# SP26_FindingTitan_Polarization_Circuit_M.net
KiCad netlist of a schematic drawn in Altium Designer
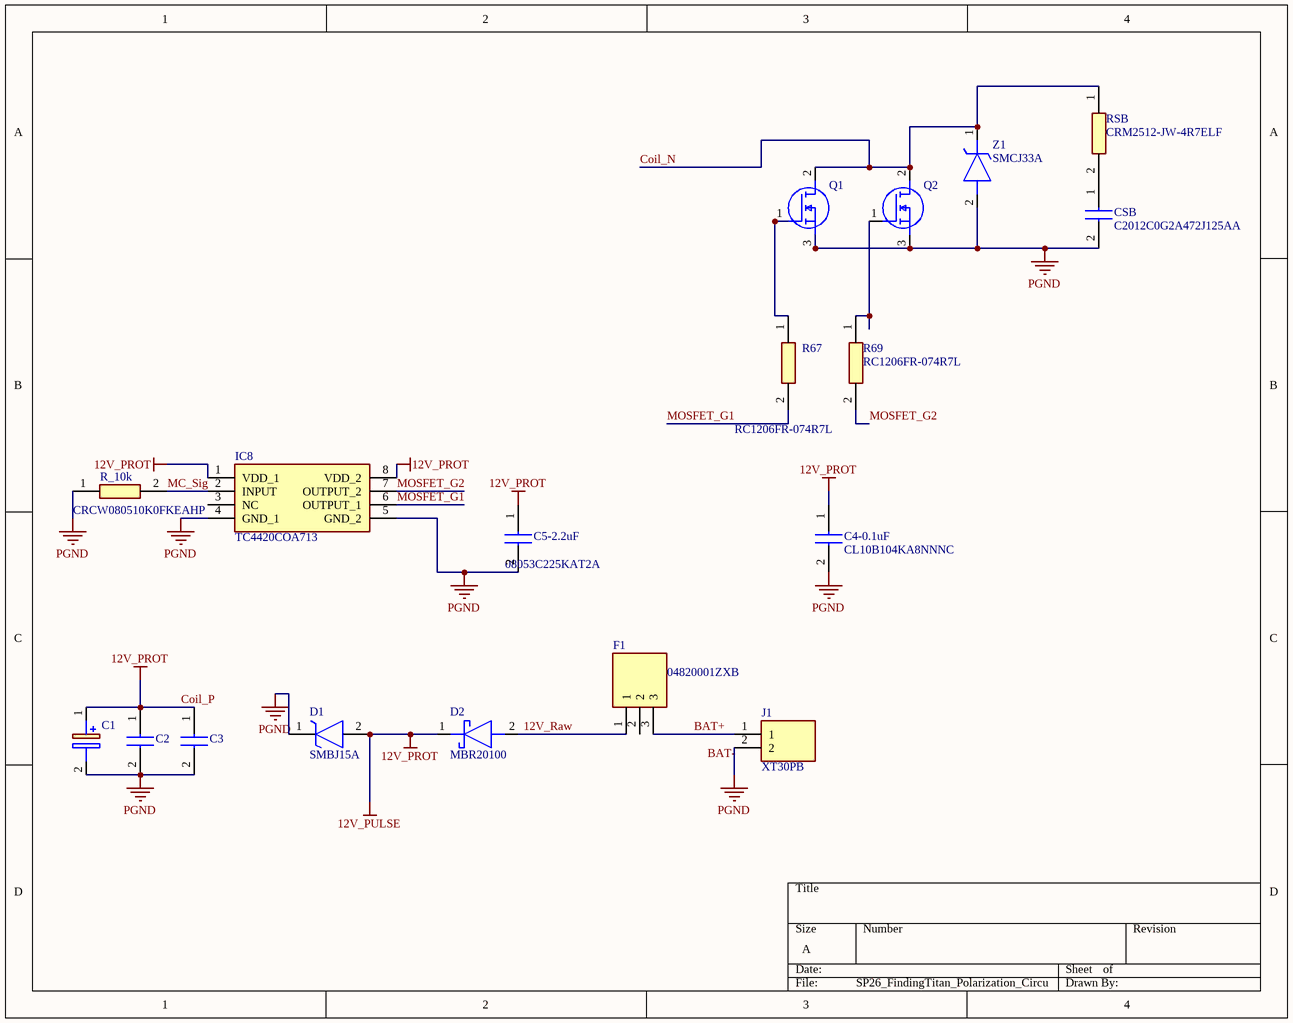
[diagram p0: SP26_FindingTitan_Polarization_Circuit_Mason_Lebens (2).SchDoc]

(export (version "E")
  (design (tool "Eeschema 10.0.6"))
  (components
    (comp (ref "C1")
      (value "EEU-FR1V102")
      (footprint "SamacSys:CAPPRD500W65D1250H2200")
      (description "Capacitor Polarised")
      (fields (field (name "MOUSER PART NUMBER") "667-EEU-FR1V102"))
      (libsource (lib "*") (part "EEU-FR1V102"))
    )
    (comp (ref "C2")
      (value "GRM21BR71H105KA12L")
      (footprint "SamacSys:CAPC2012X145N")
      (description "Capacitor")
      (fields (field (name "MOUSER PART NUMBER") "81-GRM21BR71H105KA2L"))
      (libsource (lib "*") (part "GRM21BR71H105KA12L"))
    )
    (comp (ref "C3")
      (value "GRM21BR71H104KA01L")
      (footprint "SamacSys:CAPC2012X145N")
      (description "Capacitor")
      (fields (field (name "MOUSER PART NUMBER") "81-GRM40X104K50L"))
      (libsource (lib "*") (part "GRM21BR71H104KA01L"))
    )
    (comp (ref "C4-0.1uF")
      (value "CL10B104KA8NNNC")
      (footprint "SamacSys:CAPC1608X90N")
      (description "Capacitor")
      (fields (field (name "MOUSER PART NUMBER") "187-CL10B104KA8NNNC"))
      (libsource (lib "*") (part "CL10B104KA8NNNC"))
    )
    (comp (ref "C5-2.2uF")
      (value "08053C225KAT2A")
      (footprint "SamacSys:CAPC2012X152N")
      (description "Capacitor")
      (fields (field (name "MOUSER PART NUMBER") "581-08053C225K"))
      (libsource (lib "*") (part "08053C225KAT2A"))
    )
    (comp (ref "CSB")
      (value "C2012C0G2A472J125AA")
      (footprint "SamacSys:CAPC2012X145N")
      (description "Capacitor")
      (fields (field (name "MOUSER PART NUMBER") "810-C2012C0G2A472J"))
      (libsource (lib "*") (part "C2012C0G2A472J125AA"))
    )
    (comp (ref "D1")
      (value "SMBJ15A")
      (footprint "SamacSys:DIOM5436X244N")
      (description "TVS Diode (Uni-directional)")
      (fields (field (name "MOUSER PART NUMBER") "78-SMBJ15A"))
      (libsource (lib "*") (part "SMBJ15A"))
    )
    (comp (ref "D2")
      (value "MBR20100")
      (footprint "SamacSys:TO508P485X1018X1930-2P")
      (description "Schottky Diode")
      (libsource (lib "*") (part "MBR20100"))
    )
    (comp (ref "F1")
      (value "04820001ZXB")
      (footprint "SamacSys:482-15A-PCB")
      (description "Fuse")
      (fields (field (name "MOUSER PART NUMBER") "576-04820001ZXB"))
      (libsource (lib "*") (part "04820001ZXB"))
    )
    (comp (ref "IC8")
      (value "TC4420COA713")
      (footprint "SamacSys:SOIC127P600X175-8N")
      (description "Integrated Circuit")
      (fields (field (name "MOUSER PART NUMBER") "579-TC4420COA713"))
      (libsource (lib "*") (part "TC4420COA713"))
    )
    (comp (ref "J1")
      (value "XT30PB")
      (footprint "SamacSys:XT30PB")
      (description "Connector")
      (libsource (lib "*") (part "XT30PB"))
    )
    (comp (ref "Q1")
      (value "IPB017N10N5LFATMA1")
      (footprint "PG-TO263-7-3_3")
      (description "MOSFET (N-Channel)")
      (fields
        (field (name "MANUFACTURER_PART_NUMBER") "IPB020N10N5LFATMA1")
        (field (name "MOUSER PART NUMBER") "726-IPB020N10N5LFATM")
      )
      (libsource (lib "*") (part "IPB020N10N5LFATMA1"))
    )
    (comp (ref "Q2")
      (value "IPB017N10N5LFATMA1")
      (footprint "PG-TO263-7-3_3")
      (description "MOSFET (N-Channel)")
      (fields
        (field (name "MANUFACTURER_PART_NUMBER") "IPB020N10N5LFATMA1")
        (field (name "MOUSER PART NUMBER") "726-IPB020N10N5LFATM")
      )
      (libsource (lib "*") (part "IPB020N10N5LFATMA1"))
    )
    (comp (ref "R67")
      (value "RC1206FR-074R7L")
      (footprint "SamacSys:RESC3116X65N")
      (description "Resistor")
      (fields (field (name "MOUSER PART NUMBER") "603-RC1206FR-074R7L"))
      (libsource (lib "*") (part "RC1206FR-074R7L"))
    )
    (comp (ref "R69")
      (value "RC1206FR-074R7L")
      (footprint "SamacSys:RESC3116X65N")
      (description "Resistor")
      (fields (field (name "MOUSER PART NUMBER") "603-RC1206FR-074R7L"))
      (libsource (lib "*") (part "RC1206FR-074R7L"))
    )
    (comp (ref "RSB")
      (value "CRM2512-JW-4R7ELF")
      (footprint "SamacSys:RESC6331X80N")
      (description "Resistor")
      (fields (field (name "MOUSER PART NUMBER") "652-CRM2512JW4R7ELF"))
      (libsource (lib "*") (part "CRM2512-JW-4R7ELF"))
    )
    (comp (ref "R_10k")
      (value "CRCW080510K0FKEAHP")
      (footprint "SamacSys:RESC2012X60N")
      (description "Resistor")
      (fields (field (name "MOUSER PART NUMBER") "71-CRCW080510K0FKEAH"))
      (libsource (lib "*") (part "CRCW080510K0FKEAHP"))
    )
    (comp (ref "Z1")
      (value "SMCJ33A")
      (footprint "SamacSys:DIOM7969X262N")
      (description "Zener Diode")
      (fields (field (name "MOUSER PART NUMBER") "576-SMCJ33A"))
      (libsource (lib "*") (part "SMCJ33A"))
    )
  )
  (nets
    (net (code "1") (name "/12V_Raw") (class "Default")
      (node (ref "D2") (pin "2") (pinfunction "A_2") (pintype "passive"))
      (node (ref "F1") (pin "1") (pinfunction "1_1") (pintype "passive"))
    )
    (net (code "2") (name "/BAT+") (class "Default")
      (node (ref "F1") (pin "3") (pinfunction "3_3") (pintype "passive"))
      (node (ref "J1") (pin "1") (pinfunction "1_1") (pintype "passive"))
    )
    (net (code "4") (name "/Coil_N") (class "Default")
      (node (ref "Q1") (pin "2") (pinfunction "D_2") (pintype "passive"))
      (node (ref "Q2") (pin "2") (pinfunction "D_2") (pintype "passive"))
      (node (ref "RSB") (pin "1") (pinfunction "1_1") (pintype "passive"))
      (node (ref "Z1") (pin "1") (pinfunction "K_1") (pintype "passive"))
    )
    (net (code "5") (name "/MC_Sig") (class "Default")
      (node (ref "IC8") (pin "2") (pinfunction "INPUT_2") (pintype "passive"))
      (node (ref "R_10k") (pin "2") (pinfunction "2_2") (pintype "passive"))
    )
    (net (code "6") (name "/MOSFET_G1") (class "Default")
      (node (ref "IC8") (pin "6") (pinfunction "OUTPUT_1_6") (pintype "passive"))
      (node (ref "R67") (pin "2") (pinfunction "2_2") (pintype "passive"))
    )
    (net (code "7") (name "/MOSFET_G2") (class "Default")
      (node (ref "IC8") (pin "7") (pinfunction "OUTPUT_2_7") (pintype "passive"))
      (node (ref "R69") (pin "2") (pinfunction "2_2") (pintype "passive"))
    )
    (net (code "8") (name "12V_PROT") (class "Default")
      (node (ref "C1") (pin "1") (pinfunction "+_1") (pintype "passive"))
      (node (ref "C2") (pin "1") (pinfunction "1_1") (pintype "passive"))
      (node (ref "C3") (pin "1") (pinfunction "1_1") (pintype "passive"))
      (node (ref "C4-0.1uF") (pin "1") (pinfunction "1_1") (pintype "passive"))
      (node (ref "C5-2.2uF") (pin "1") (pinfunction "1_1") (pintype "passive"))
      (node (ref "D1") (pin "2") (pinfunction "A_2") (pintype "passive"))
      (node (ref "D2") (pin "1") (pinfunction "K_1") (pintype "passive"))
      (node (ref "IC8") (pin "1") (pinfunction "VDD_1_1") (pintype "passive"))
      (node (ref "IC8") (pin "8") (pinfunction "VDD_2_8") (pintype "passive"))
    )
    (net (code "9") (name "Net-(CSB-Pad1)") (class "Default")
      (node (ref "CSB") (pin "1") (pinfunction "1_1") (pintype "passive"))
      (node (ref "RSB") (pin "2") (pinfunction "2_2") (pintype "passive"))
    )
    (net (code "10") (name "Net-(Q1-G)") (class "Default")
      (node (ref "Q1") (pin "1") (pinfunction "G_1") (pintype "passive"))
      (node (ref "R67") (pin "1") (pinfunction "1_1") (pintype "passive"))
    )
    (net (code "11") (name "Net-(Q2-G)") (class "Default")
      (node (ref "Q2") (pin "1") (pinfunction "G_1") (pintype "passive"))
      (node (ref "R69") (pin "1") (pinfunction "1_1") (pintype "passive"))
    )
    (net (code "12") (name "PGND") (class "Default")
      (node (ref "C1") (pin "2") (pinfunction "-_2") (pintype "passive"))
      (node (ref "C2") (pin "2") (pinfunction "2_2") (pintype "passive"))
      (node (ref "C3") (pin "2") (pinfunction "2_2") (pintype "passive"))
      (node (ref "C4-0.1uF") (pin "2") (pinfunction "2_2") (pintype "passive"))
      (node (ref "C5-2.2uF") (pin "2") (pinfunction "2_2") (pintype "passive"))
      (node (ref "CSB") (pin "2") (pinfunction "2_2") (pintype "passive"))
      (node (ref "D1") (pin "1") (pinfunction "K_1") (pintype "passive"))
      (node (ref "IC8") (pin "4") (pinfunction "GND_1_4") (pintype "passive"))
      (node (ref "IC8") (pin "5") (pinfunction "GND_2_5") (pintype "passive"))
      (node (ref "J1") (pin "2") (pinfunction "2_2") (pintype "passive"))
      (node (ref "Q1") (pin "3") (pinfunction "S_3") (pintype "passive"))
      (node (ref "Q2") (pin "3") (pinfunction "S_3") (pintype "passive"))
      (node (ref "R_10k") (pin "1") (pinfunction "1_1") (pintype "passive"))
      (node (ref "Z1") (pin "2") (pinfunction "A_2") (pintype "passive"))
    )
    (net (code "13") (name "unconnected-(F1-Pad2)") (class "Default")
      (node (ref "F1") (pin "2") (pinfunction "2_2") (pintype "passive"))
    )
    (net (code "14") (name "unconnected-(IC8-NC-Pad3)") (class "Default")
      (node (ref "IC8") (pin "3") (pinfunction "NC_3") (pintype "passive"))
    )
  )
)
